# Kenbak-nanoduino_v2_001.net
KiCad netlist of a schematic drawn in EAGLE
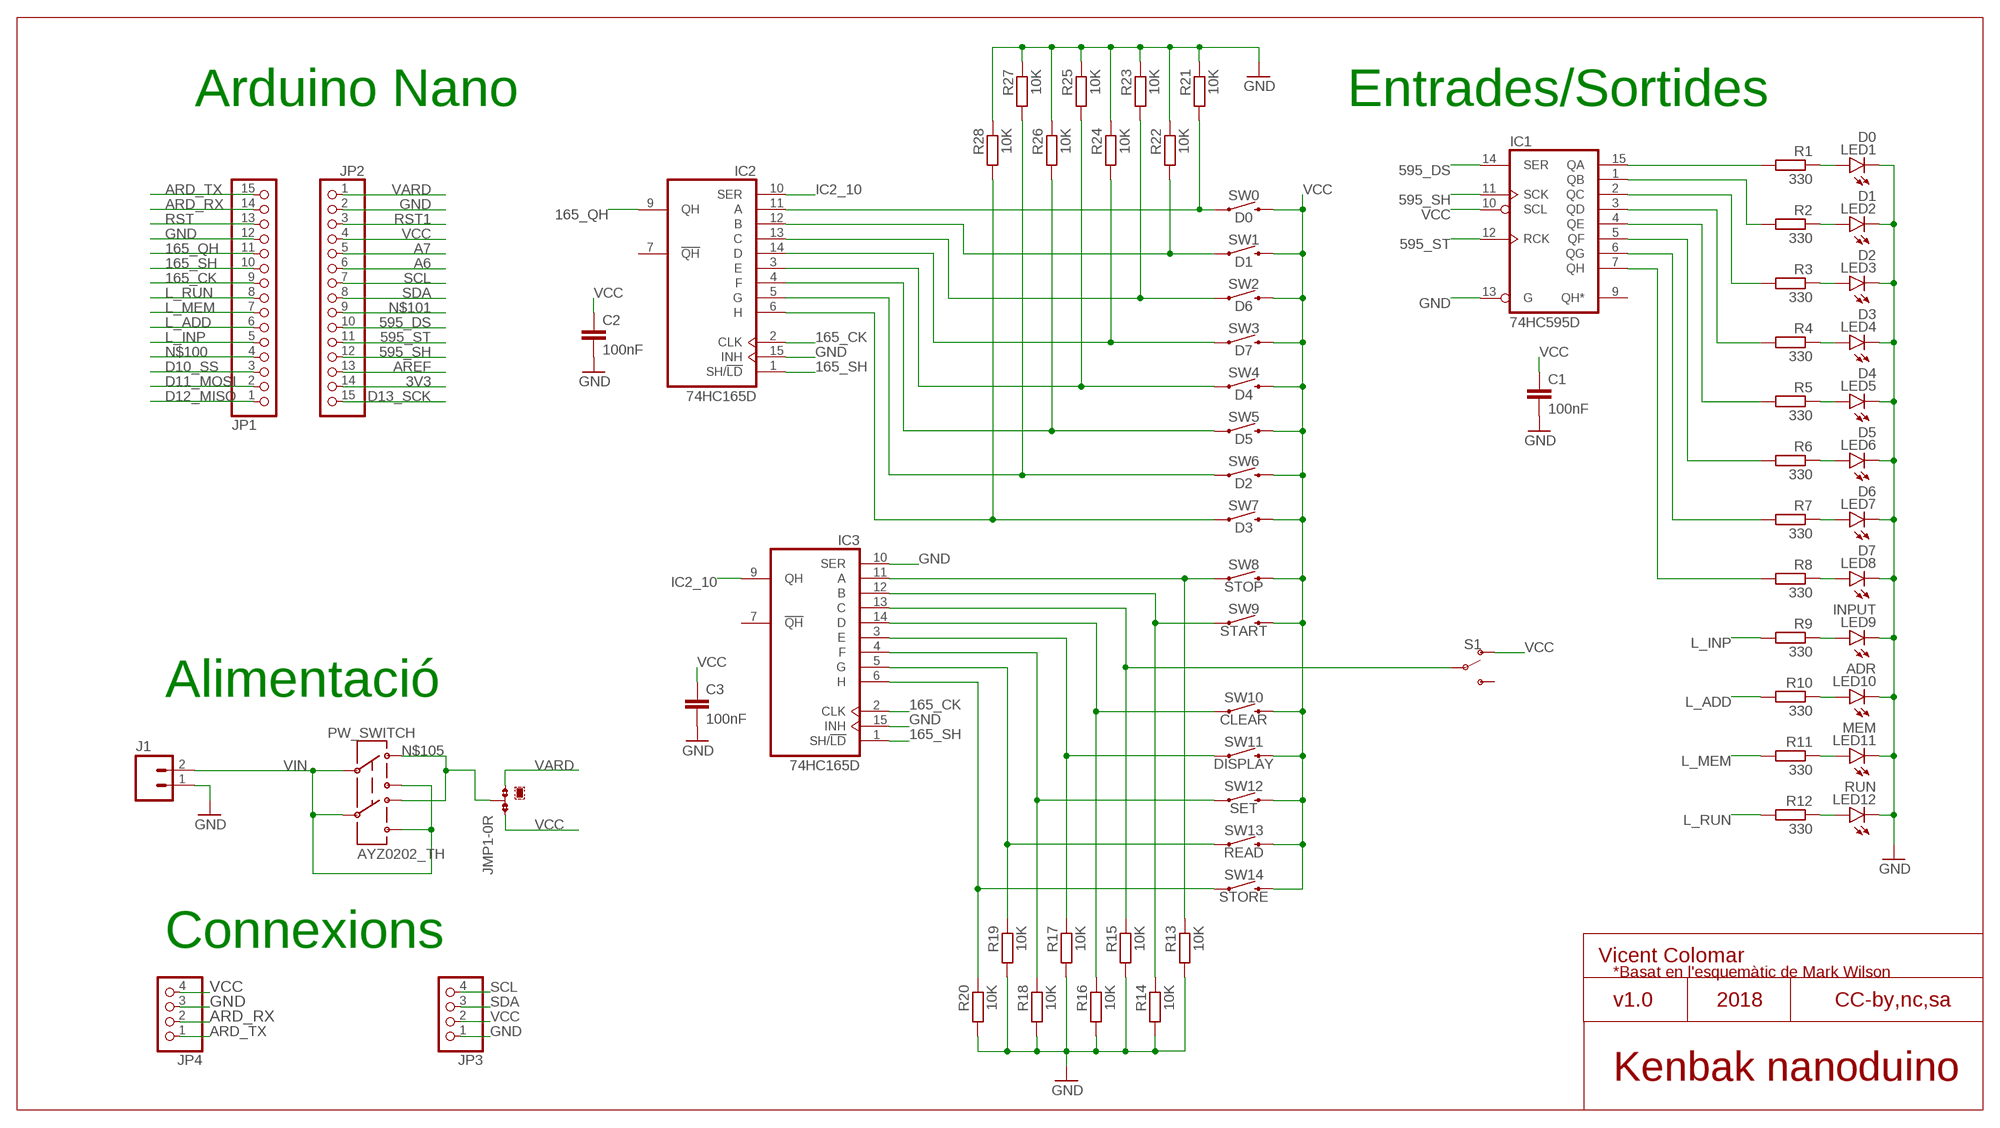
[diagram p0: schematic, sheet 1]

(export (version "E")
  (design (tool "Eeschema 10.0.6"))
  (components
    (comp (ref "C1")
      (value "100nF")
      (footprint "eagle-import:C1206")
      (libsource (lib "eagle-import") (part "C-EUC1206"))
    )
    (comp (ref "C2")
      (value "100nF")
      (footprint "eagle-import:C1206")
      (libsource (lib "eagle-import") (part "C-EUC1206"))
    )
    (comp (ref "C3")
      (value "100nF")
      (footprint "eagle-import:C1206")
      (libsource (lib "eagle-import") (part "C-EUC1206"))
    )
    (comp (ref "IC1")
      (value "74HC595D")
      (footprint "eagle-import:SO16")
      (libsource (lib "eagle-import") (part "74595DHC"))
    )
    (comp (ref "IC2")
      (value "74HC165D")
      (footprint "eagle-import:SO16")
      (libsource (lib "eagle-import") (part "74165DHC"))
    )
    (comp (ref "IC3")
      (value "74HC165D")
      (footprint "eagle-import:SO16")
      (libsource (lib "eagle-import") (part "74165DHC"))
    )
    (comp (ref "J1")
      (value "M02LOCK_LONGPADS")
      (footprint "eagle-import:1X02_LOCK_LONGPADS")
      (libsource (lib "eagle-import") (part "M02LOCK_LONGPADS"))
    )
    (comp (ref "JMP1")
      (value "0R-JUMPA")
      (footprint "eagle-import:A0R-JMP")
      (libsource (lib "eagle-import") (part "0R-JUMPA"))
    )
    (comp (ref "JP1")
      (value "PINHD-1X15_2.54-SMD")
      (footprint "eagle-import:1X15SMD")
      (libsource (lib "eagle-import") (part "PINHD-1X15_2.54-SMD"))
    )
    (comp (ref "JP2")
      (value "PINHD-1X15_2.54-SMD")
      (footprint "eagle-import:1X15SMD")
      (libsource (lib "eagle-import") (part "PINHD-1X15_2.54-SMD"))
    )
    (comp (ref "JP3")
      (value "PINHD-1X04_2.54-SMD")
      (footprint "eagle-import:1X04SMD")
      (libsource (lib "eagle-import") (part "PINHD-1X04_2.54-SMD"))
    )
    (comp (ref "JP4")
      (value "PINHD-1X04_2.54-SMD")
      (footprint "eagle-import:1X04SMD")
      (libsource (lib "eagle-import") (part "PINHD-1X04_2.54-SMD"))
    )
    (comp (ref "LED1")
      (value "D0")
      (footprint "eagle-import:LED3MM")
      (libsource (lib "eagle-import") (part "LED3MM"))
    )
    (comp (ref "LED2")
      (value "D1")
      (footprint "eagle-import:LED3MM")
      (libsource (lib "eagle-import") (part "LED3MM"))
    )
    (comp (ref "LED3")
      (value "D2")
      (footprint "eagle-import:LED3MM")
      (libsource (lib "eagle-import") (part "LED3MM"))
    )
    (comp (ref "LED4")
      (value "D3")
      (footprint "eagle-import:LED3MM")
      (libsource (lib "eagle-import") (part "LED3MM"))
    )
    (comp (ref "LED5")
      (value "D4")
      (footprint "eagle-import:LED3MM")
      (libsource (lib "eagle-import") (part "LED3MM"))
    )
    (comp (ref "LED6")
      (value "D5")
      (footprint "eagle-import:LED3MM")
      (libsource (lib "eagle-import") (part "LED3MM"))
    )
    (comp (ref "LED7")
      (value "D6")
      (footprint "eagle-import:LED3MM")
      (libsource (lib "eagle-import") (part "LED3MM"))
    )
    (comp (ref "LED8")
      (value "D7")
      (footprint "eagle-import:LED3MM")
      (libsource (lib "eagle-import") (part "LED3MM"))
    )
    (comp (ref "LED9")
      (value "INPUT")
      (footprint "eagle-import:LED3MM")
      (libsource (lib "eagle-import") (part "LED3MM"))
    )
    (comp (ref "LED10")
      (value "ADR")
      (footprint "eagle-import:LED3MM")
      (libsource (lib "eagle-import") (part "LED3MM"))
    )
    (comp (ref "LED11")
      (value "MEM")
      (footprint "eagle-import:LED3MM")
      (libsource (lib "eagle-import") (part "LED3MM"))
    )
    (comp (ref "LED12")
      (value "RUN")
      (footprint "eagle-import:LED3MM")
      (libsource (lib "eagle-import") (part "LED3MM"))
    )
    (comp (ref "PW_SWITCH")
      (value "AYZ0202_TH")
      (footprint "eagle-import:AYZ0202_TH")
      (libsource (lib "eagle-import") (part "AYZ0202_TH"))
    )
    (comp (ref "R1")
      (value "330")
      (footprint "eagle-import:R1206")
      (libsource (lib "eagle-import") (part "R-EU_R1206"))
    )
    (comp (ref "R2")
      (value "330")
      (footprint "eagle-import:R1206")
      (libsource (lib "eagle-import") (part "R-EU_R1206"))
    )
    (comp (ref "R3")
      (value "330")
      (footprint "eagle-import:R1206")
      (libsource (lib "eagle-import") (part "R-EU_R1206"))
    )
    (comp (ref "R4")
      (value "330")
      (footprint "eagle-import:R1206")
      (libsource (lib "eagle-import") (part "R-EU_R1206"))
    )
    (comp (ref "R5")
      (value "330")
      (footprint "eagle-import:R1206")
      (libsource (lib "eagle-import") (part "R-EU_R1206"))
    )
    (comp (ref "R6")
      (value "330")
      (footprint "eagle-import:R1206")
      (libsource (lib "eagle-import") (part "R-EU_R1206"))
    )
    (comp (ref "R7")
      (value "330")
      (footprint "eagle-import:R1206")
      (libsource (lib "eagle-import") (part "R-EU_R1206"))
    )
    (comp (ref "R8")
      (value "330")
      (footprint "eagle-import:R1206")
      (libsource (lib "eagle-import") (part "R-EU_R1206"))
    )
    (comp (ref "R9")
      (value "330")
      (footprint "eagle-import:R1206")
      (libsource (lib "eagle-import") (part "R-EU_R1206"))
    )
    (comp (ref "R10")
      (value "330")
      (footprint "eagle-import:R1206")
      (libsource (lib "eagle-import") (part "R-EU_R1206"))
    )
    (comp (ref "R11")
      (value "330")
      (footprint "eagle-import:R1206")
      (libsource (lib "eagle-import") (part "R-EU_R1206"))
    )
    (comp (ref "R12")
      (value "330")
      (footprint "eagle-import:R1206")
      (libsource (lib "eagle-import") (part "R-EU_R1206"))
    )
    (comp (ref "R13")
      (value "10K")
      (footprint "eagle-import:R1206")
      (libsource (lib "eagle-import") (part "R-EU_R1206"))
    )
    (comp (ref "R14")
      (value "10K")
      (footprint "eagle-import:R1206")
      (libsource (lib "eagle-import") (part "R-EU_R1206"))
    )
    (comp (ref "R15")
      (value "10K")
      (footprint "eagle-import:R1206")
      (libsource (lib "eagle-import") (part "R-EU_R1206"))
    )
    (comp (ref "R16")
      (value "10K")
      (footprint "eagle-import:R1206")
      (libsource (lib "eagle-import") (part "R-EU_R1206"))
    )
    (comp (ref "R17")
      (value "10K")
      (footprint "eagle-import:R1206")
      (libsource (lib "eagle-import") (part "R-EU_R1206"))
    )
    (comp (ref "R18")
      (value "10K")
      (footprint "eagle-import:R1206")
      (libsource (lib "eagle-import") (part "R-EU_R1206"))
    )
    (comp (ref "R19")
      (value "10K")
      (footprint "eagle-import:R1206")
      (libsource (lib "eagle-import") (part "R-EU_R1206"))
    )
    (comp (ref "R20")
      (value "10K")
      (footprint "eagle-import:R1206")
      (libsource (lib "eagle-import") (part "R-EU_R1206"))
    )
    (comp (ref "R21")
      (value "10K")
      (footprint "eagle-import:R1206")
      (libsource (lib "eagle-import") (part "R-EU_R1206"))
    )
    (comp (ref "R22")
      (value "10K")
      (footprint "eagle-import:R1206")
      (libsource (lib "eagle-import") (part "R-EU_R1206"))
    )
    (comp (ref "R23")
      (value "10K")
      (footprint "eagle-import:R1206")
      (libsource (lib "eagle-import") (part "R-EU_R1206"))
    )
    (comp (ref "R24")
      (value "10K")
      (footprint "eagle-import:R1206")
      (libsource (lib "eagle-import") (part "R-EU_R1206"))
    )
    (comp (ref "R25")
      (value "10K")
      (footprint "eagle-import:R1206")
      (libsource (lib "eagle-import") (part "R-EU_R1206"))
    )
    (comp (ref "R26")
      (value "10K")
      (footprint "eagle-import:R1206")
      (libsource (lib "eagle-import") (part "R-EU_R1206"))
    )
    (comp (ref "R27")
      (value "10K")
      (footprint "eagle-import:R1206")
      (libsource (lib "eagle-import") (part "R-EU_R1206"))
    )
    (comp (ref "R28")
      (value "10K")
      (footprint "eagle-import:R1206")
      (libsource (lib "eagle-import") (part "R-EU_R1206"))
    )
    (comp (ref "S1")
      (value "SWITCH-SPDT-PTH-11.6X4.0MM")
      (footprint "eagle-import:SWITCH_SPDT_PTH_11.6X4.0MM")
      (libsource (lib "eagle-import") (part "SWITCH-SPDT-PTH-11.6X4.0MM"))
    )
    (comp (ref "SW0")
      (value "D0")
      (footprint "eagle-import:TACTILE_SWITCH_SMD_6.0X3.5MM")
      (libsource (lib "eagle-import") (part "BOTOSMD"))
    )
    (comp (ref "SW1")
      (value "D1")
      (footprint "eagle-import:TACTILE_SWITCH_SMD_6.0X3.5MM")
      (libsource (lib "eagle-import") (part "BOTOSMD"))
    )
    (comp (ref "SW2")
      (value "D6")
      (footprint "eagle-import:TACTILE_SWITCH_SMD_6.0X3.5MM")
      (libsource (lib "eagle-import") (part "BOTOSMD"))
    )
    (comp (ref "SW3")
      (value "D7")
      (footprint "eagle-import:TACTILE_SWITCH_SMD_6.0X3.5MM")
      (libsource (lib "eagle-import") (part "BOTOSMD"))
    )
    (comp (ref "SW4")
      (value "D4")
      (footprint "eagle-import:TACTILE_SWITCH_SMD_6.0X3.5MM")
      (libsource (lib "eagle-import") (part "BOTOSMD"))
    )
    (comp (ref "SW5")
      (value "D5")
      (footprint "eagle-import:TACTILE_SWITCH_SMD_6.0X3.5MM")
      (libsource (lib "eagle-import") (part "BOTOSMD"))
    )
    (comp (ref "SW6")
      (value "D2")
      (footprint "eagle-import:TACTILE_SWITCH_SMD_6.0X3.5MM")
      (libsource (lib "eagle-import") (part "BOTOSMD"))
    )
    (comp (ref "SW7")
      (value "D3")
      (footprint "eagle-import:TACTILE_SWITCH_SMD_6.0X3.5MM")
      (libsource (lib "eagle-import") (part "BOTOSMD"))
    )
    (comp (ref "SW8")
      (value "STOP")
      (footprint "eagle-import:TACTILE_SWITCH_SMD_6.0X3.5MM")
      (libsource (lib "eagle-import") (part "BOTOSMD"))
    )
    (comp (ref "SW9")
      (value "START")
      (footprint "eagle-import:TACTILE_SWITCH_SMD_6.0X3.5MM")
      (libsource (lib "eagle-import") (part "BOTOSMD"))
    )
    (comp (ref "SW10")
      (value "CLEAR")
      (footprint "eagle-import:TACTILE_SWITCH_SMD_6.0X3.5MM")
      (libsource (lib "eagle-import") (part "BOTOSMD"))
    )
    (comp (ref "SW11")
      (value "DISPLAY")
      (footprint "eagle-import:TACTILE_SWITCH_SMD_6.0X3.5MM")
      (libsource (lib "eagle-import") (part "BOTOSMD"))
    )
    (comp (ref "SW12")
      (value "SET")
      (footprint "eagle-import:TACTILE_SWITCH_SMD_6.0X3.5MM")
      (libsource (lib "eagle-import") (part "BOTOSMD"))
    )
    (comp (ref "SW13")
      (value "READ")
      (footprint "eagle-import:TACTILE_SWITCH_SMD_6.0X3.5MM")
      (libsource (lib "eagle-import") (part "BOTOSMD"))
    )
    (comp (ref "SW14")
      (value "STORE")
      (footprint "eagle-import:TACTILE_SWITCH_SMD_6.0X3.5MM")
      (libsource (lib "eagle-import") (part "BOTOSMD"))
    )
  )
  (nets
    (net (code "1") (name "/3V3") (class "Default")
      (node (ref "JP2") (pin "14") (pinfunction "14_14") (pintype "passive"))
    )
    (net (code "2") (name "/165_CK") (class "Default")
      (node (ref "IC2") (pin "2") (pinfunction "CLK_2") (pintype "input"))
      (node (ref "IC3") (pin "2") (pinfunction "CLK_2") (pintype "input"))
      (node (ref "JP1") (pin "9") (pinfunction "9_9") (pintype "passive"))
    )
    (net (code "3") (name "/165_QH") (class "Default")
      (node (ref "IC2") (pin "9") (pinfunction "QH_9") (pintype "output"))
      (node (ref "JP1") (pin "11") (pinfunction "11_11") (pintype "passive"))
    )
    (net (code "4") (name "/165_SH") (class "Default")
      (node (ref "IC2") (pin "1") (pinfunction "SH/~{LD}_1") (pintype "input"))
      (node (ref "IC3") (pin "1") (pinfunction "SH/~{LD}_1") (pintype "input"))
      (node (ref "JP1") (pin "10") (pinfunction "10_10") (pintype "passive"))
    )
    (net (code "5") (name "/595_DS") (class "Default")
      (node (ref "IC1") (pin "14") (pinfunction "SER_14") (pintype "input"))
      (node (ref "JP2") (pin "10") (pinfunction "10_10") (pintype "passive"))
    )
    (net (code "6") (name "/595_SH") (class "Default")
      (node (ref "IC1") (pin "11") (pinfunction "SCK_11") (pintype "input"))
      (node (ref "JP2") (pin "12") (pinfunction "12_12") (pintype "passive"))
    )
    (net (code "7") (name "/595_ST") (class "Default")
      (node (ref "IC1") (pin "12") (pinfunction "RCK_12") (pintype "input"))
      (node (ref "JP2") (pin "11") (pinfunction "11_11") (pintype "passive"))
    )
    (net (code "8") (name "/A6") (class "Default")
      (node (ref "JP2") (pin "6") (pinfunction "6_6") (pintype "passive"))
    )
    (net (code "9") (name "/A7") (class "Default")
      (node (ref "JP2") (pin "5") (pinfunction "5_5") (pintype "passive"))
    )
    (net (code "10") (name "/ARD_RX") (class "Default")
      (node (ref "JP1") (pin "14") (pinfunction "14_14") (pintype "passive"))
      (node (ref "JP4") (pin "2") (pinfunction "2_2") (pintype "passive"))
    )
    (net (code "11") (name "/ARD_TX") (class "Default")
      (node (ref "JP1") (pin "15") (pinfunction "15_15") (pintype "passive"))
      (node (ref "JP4") (pin "1") (pinfunction "1_1") (pintype "passive"))
    )
    (net (code "12") (name "/AREF") (class "Default")
      (node (ref "JP2") (pin "13") (pinfunction "13_13") (pintype "passive"))
    )
    (net (code "13") (name "/D10_SS") (class "Default")
      (node (ref "JP1") (pin "3") (pinfunction "3_3") (pintype "passive"))
    )
    (net (code "14") (name "/D11_MOSI") (class "Default")
      (node (ref "JP1") (pin "2") (pinfunction "2_2") (pintype "passive"))
    )
    (net (code "15") (name "/D12_MISO") (class "Default")
      (node (ref "JP1") (pin "1") (pinfunction "1_1") (pintype "passive"))
    )
    (net (code "16") (name "/D13_SCK") (class "Default")
      (node (ref "JP2") (pin "15") (pinfunction "15_15") (pintype "passive"))
    )
    (net (code "17") (name "/IC2_10") (class "Default")
      (node (ref "IC2") (pin "10") (pinfunction "SER_10") (pintype "input"))
      (node (ref "IC3") (pin "9") (pinfunction "QH_9") (pintype "output"))
    )
    (net (code "18") (name "/L_ADD") (class "Default")
      (node (ref "JP1") (pin "6") (pinfunction "6_6") (pintype "passive"))
      (node (ref "R10") (pin "2") (pinfunction "2_2") (pintype "passive"))
    )
    (net (code "19") (name "/L_INP") (class "Default")
      (node (ref "JP1") (pin "5") (pinfunction "5_5") (pintype "passive"))
      (node (ref "R9") (pin "2") (pinfunction "2_2") (pintype "passive"))
    )
    (net (code "20") (name "/L_MEM") (class "Default")
      (node (ref "JP1") (pin "7") (pinfunction "7_7") (pintype "passive"))
      (node (ref "R11") (pin "2") (pinfunction "2_2") (pintype "passive"))
    )
    (net (code "21") (name "/L_RUN") (class "Default")
      (node (ref "JP1") (pin "8") (pinfunction "8_8") (pintype "passive"))
      (node (ref "R12") (pin "2") (pinfunction "2_2") (pintype "passive"))
    )
    (net (code "22") (name "/N$100") (class "Default")
      (node (ref "JP1") (pin "4") (pinfunction "4_4") (pintype "passive"))
    )
    (net (code "23") (name "/N$101") (class "Default")
      (node (ref "JP2") (pin "9") (pinfunction "9_9") (pintype "passive"))
    )
    (net (code "24") (name "/N$105") (class "Default")
      (node (ref "JMP1") (pin "2") (pinfunction "2_2") (pintype "passive"))
      (node (ref "PW_SWITCH") (pin "D1") (pinfunction "D1_D1") (pintype "bidirectional"))
      (node (ref "PW_SWITCH") (pin "D2") (pinfunction "D2_D2") (pintype "bidirectional"))
    )
    (net (code "25") (name "/RST") (class "Default")
      (node (ref "JP1") (pin "13") (pinfunction "13_13") (pintype "passive"))
    )
    (net (code "26") (name "/RST1") (class "Default")
      (node (ref "JP2") (pin "3") (pinfunction "3_3") (pintype "passive"))
    )
    (net (code "27") (name "/SCL") (class "Default")
      (node (ref "JP2") (pin "7") (pinfunction "7_7") (pintype "passive"))
      (node (ref "JP3") (pin "4") (pinfunction "4_4") (pintype "passive"))
    )
    (net (code "28") (name "/SDA") (class "Default")
      (node (ref "JP2") (pin "8") (pinfunction "8_8") (pintype "passive"))
      (node (ref "JP3") (pin "3") (pinfunction "3_3") (pintype "passive"))
    )
    (net (code "29") (name "/VARD") (class "Default")
      (node (ref "JMP1") (pin "3") (pinfunction "3_3") (pintype "passive"))
      (node (ref "JP2") (pin "1") (pinfunction "1_1") (pintype "passive"))
    )
    (net (code "30") (name "/VCC") (class "Default")
      (node (ref "C1") (pin "1") (pinfunction "1_1") (pintype "passive"))
      (node (ref "C2") (pin "1") (pinfunction "1_1") (pintype "passive"))
      (node (ref "C3") (pin "1") (pinfunction "1_1") (pintype "passive"))
      (node (ref "IC1") (pin "10") (pinfunction "SCL_10") (pintype "input"))
      (node (ref "JMP1") (pin "1") (pinfunction "1_1") (pintype "passive"))
      (node (ref "JP2") (pin "4") (pinfunction "4_4") (pintype "passive"))
      (node (ref "JP3") (pin "2") (pinfunction "2_2") (pintype "passive"))
      (node (ref "JP4") (pin "4") (pinfunction "4_4") (pintype "passive"))
      (node (ref "S1") (pin "1") (pinfunction "O_1") (pintype "passive"))
      (node (ref "SW0") (pin "2") (pinfunction "2_2") (pintype "passive"))
      (node (ref "SW1") (pin "2") (pinfunction "2_2") (pintype "passive"))
      (node (ref "SW10") (pin "2") (pinfunction "2_2") (pintype "passive"))
      (node (ref "SW11") (pin "2") (pinfunction "2_2") (pintype "passive"))
      (node (ref "SW12") (pin "2") (pinfunction "2_2") (pintype "passive"))
      (node (ref "SW13") (pin "2") (pinfunction "2_2") (pintype "passive"))
      (node (ref "SW14") (pin "2") (pinfunction "2_2") (pintype "passive"))
      (node (ref "SW2") (pin "2") (pinfunction "2_2") (pintype "passive"))
      (node (ref "SW3") (pin "2") (pinfunction "2_2") (pintype "passive"))
      (node (ref "SW4") (pin "2") (pinfunction "2_2") (pintype "passive"))
      (node (ref "SW5") (pin "2") (pinfunction "2_2") (pintype "passive"))
      (node (ref "SW6") (pin "2") (pinfunction "2_2") (pintype "passive"))
      (node (ref "SW7") (pin "2") (pinfunction "2_2") (pintype "passive"))
      (node (ref "SW8") (pin "2") (pinfunction "2_2") (pintype "passive"))
      (node (ref "SW9") (pin "2") (pinfunction "2_2") (pintype "passive"))
    )
    (net (code "31") (name "/VIN") (class "Default")
      (node (ref "J1") (pin "2") (pinfunction "2_2") (pintype "passive"))
      (node (ref "PW_SWITCH") (pin "B1") (pinfunction "B1_B1") (pintype "bidirectional"))
      (node (ref "PW_SWITCH") (pin "B2") (pinfunction "B2_B2") (pintype "bidirectional"))
      (node (ref "PW_SWITCH") (pin "C1") (pinfunction "C1_C1") (pintype "bidirectional"))
      (node (ref "PW_SWITCH") (pin "C2") (pinfunction "C2_C2") (pintype "bidirectional"))
    )
    (net (code "32") (name "GND") (class "Default")
      (node (ref "C1") (pin "2") (pinfunction "2_2") (pintype "passive"))
      (node (ref "C2") (pin "2") (pinfunction "2_2") (pintype "passive"))
      (node (ref "C3") (pin "2") (pinfunction "2_2") (pintype "passive"))
      (node (ref "IC1") (pin "13") (pinfunction "G_13") (pintype "input"))
      (node (ref "IC2") (pin "15") (pinfunction "INH_15") (pintype "input"))
      (node (ref "IC3") (pin "10") (pinfunction "SER_10") (pintype "input"))
      (node (ref "IC3") (pin "15") (pinfunction "INH_15") (pintype "input"))
      (node (ref "J1") (pin "1") (pinfunction "1_1") (pintype "passive"))
      (node (ref "JP1") (pin "12") (pinfunction "12_12") (pintype "passive"))
      (node (ref "JP2") (pin "2") (pinfunction "2_2") (pintype "passive"))
      (node (ref "JP3") (pin "1") (pinfunction "1_1") (pintype "passive"))
      (node (ref "JP4") (pin "3") (pinfunction "3_3") (pintype "passive"))
      (node (ref "LED1") (pin "K") (pinfunction "C_K") (pintype "passive"))
      (node (ref "LED10") (pin "K") (pinfunction "C_K") (pintype "passive"))
      (node (ref "LED11") (pin "K") (pinfunction "C_K") (pintype "passive"))
      (node (ref "LED12") (pin "K") (pinfunction "C_K") (pintype "passive"))
      (node (ref "LED2") (pin "K") (pinfunction "C_K") (pintype "passive"))
      (node (ref "LED3") (pin "K") (pinfunction "C_K") (pintype "passive"))
      (node (ref "LED4") (pin "K") (pinfunction "C_K") (pintype "passive"))
      (node (ref "LED5") (pin "K") (pinfunction "C_K") (pintype "passive"))
      (node (ref "LED6") (pin "K") (pinfunction "C_K") (pintype "passive"))
      (node (ref "LED7") (pin "K") (pinfunction "C_K") (pintype "passive"))
      (node (ref "LED8") (pin "K") (pinfunction "C_K") (pintype "passive"))
      (node (ref "LED9") (pin "K") (pinfunction "C_K") (pintype "passive"))
      (node (ref "R13") (pin "2") (pinfunction "2_2") (pintype "passive"))
      (node (ref "R14") (pin "2") (pinfunction "2_2") (pintype "passive"))
      (node (ref "R15") (pin "2") (pinfunction "2_2") (pintype "passive"))
      (node (ref "R16") (pin "2") (pinfunction "2_2") (pintype "passive"))
      (node (ref "R17") (pin "2") (pinfunction "2_2") (pintype "passive"))
      (node (ref "R18") (pin "2") (pinfunction "2_2") (pintype "passive"))
      (node (ref "R19") (pin "2") (pinfunction "2_2") (pintype "passive"))
      (node (ref "R20") (pin "2") (pinfunction "2_2") (pintype "passive"))
      (node (ref "R21") (pin "1") (pinfunction "1_1") (pintype "passive"))
      (node (ref "R22") (pin "1") (pinfunction "1_1") (pintype "passive"))
      (node (ref "R23") (pin "1") (pinfunction "1_1") (pintype "passive"))
      (node (ref "R24") (pin "1") (pinfunction "1_1") (pintype "passive"))
      (node (ref "R25") (pin "1") (pinfunction "1_1") (pintype "passive"))
      (node (ref "R26") (pin "1") (pinfunction "1_1") (pintype "passive"))
      (node (ref "R27") (pin "1") (pinfunction "1_1") (pintype "passive"))
      (node (ref "R28") (pin "1") (pinfunction "1_1") (pintype "passive"))
    )
    (net (code "33") (name "Net-(IC1A-QA)") (class "Default")
      (node (ref "IC1") (pin "15") (pinfunction "QA_15") (pintype "tri_state"))
      (node (ref "R1") (pin "2") (pinfunction "2_2") (pintype "passive"))
    )
    (net (code "34") (name "Net-(IC1A-QB)") (class "Default")
      (node (ref "IC1") (pin "1") (pinfunction "QB_1") (pintype "tri_state"))
      (node (ref "R2") (pin "2") (pinfunction "2_2") (pintype "passive"))
    )
    (net (code "35") (name "Net-(IC1A-QC)") (class "Default")
      (node (ref "IC1") (pin "2") (pinfunction "QC_2") (pintype "tri_state"))
      (node (ref "R3") (pin "2") (pinfunction "2_2") (pintype "passive"))
    )
    (net (code "36") (name "Net-(IC1A-QD)") (class "Default")
      (node (ref "IC1") (pin "3") (pinfunction "QD_3") (pintype "tri_state"))
      (node (ref "R4") (pin "2") (pinfunction "2_2") (pintype "passive"))
    )
    (net (code "37") (name "Net-(IC1A-QE)") (class "Default")
      (node (ref "IC1") (pin "4") (pinfunction "QE_4") (pintype "tri_state"))
      (node (ref "R5") (pin "2") (pinfunction "2_2") (pintype "passive"))
    )
    (net (code "38") (name "Net-(IC1A-QF)") (class "Default")
      (node (ref "IC1") (pin "5") (pinfunction "QF_5") (pintype "tri_state"))
      (node (ref "R6") (pin "2") (pinfunction "2_2") (pintype "passive"))
    )
    (net (code "39") (name "Net-(IC1A-QG)") (class "Default")
      (node (ref "IC1") (pin "6") (pinfunction "QG_6") (pintype "tri_state"))
      (node (ref "R7") (pin "2") (pinfunction "2_2") (pintype "passive"))
    )
    (net (code "40") (name "Net-(IC1A-QH)") (class "Default")
      (node (ref "IC1") (pin "7") (pinfunction "QH_7") (pintype "tri_state"))
      (node (ref "R8") (pin "2") (pinfunction "2_2") (pintype "passive"))
    )
    (net (code "41") (name "Net-(IC2A-A)") (class "Default")
      (node (ref "IC2") (pin "11") (pinfunction "A_11") (pintype "input"))
      (node (ref "R21") (pin "2") (pinfunction "2_2") (pintype "passive"))
      (node (ref "SW0") (pin "1") (pinfunction "1_1") (pintype "passive"))
    )
    (net (code "42") (name "Net-(IC2A-B)") (class "Default")
      (node (ref "IC2") (pin "12") (pinfunction "B_12") (pintype "input"))
      (node (ref "R22") (pin "2") (pinfunction "2_2") (pintype "passive"))
      (node (ref "SW1") (pin "1") (pinfunction "1_1") (pintype "passive"))
    )
    (net (code "43") (name "Net-(IC2A-C)") (class "Default")
      (node (ref "IC2") (pin "13") (pinfunction "C_13") (pintype "input"))
      (node (ref "R23") (pin "2") (pinfunction "2_2") (pintype "passive"))
      (node (ref "SW2") (pin "1") (pinfunction "1_1") (pintype "passive"))
    )
    (net (code "44") (name "Net-(IC2A-D)") (class "Default")
      (node (ref "IC2") (pin "14") (pinfunction "D_14") (pintype "input"))
      (node (ref "R24") (pin "2") (pinfunction "2_2") (pintype "passive"))
      (node (ref "SW3") (pin "1") (pinfunction "1_1") (pintype "passive"))
    )
    (net (code "45") (name "Net-(IC2A-E)") (class "Default")
      (node (ref "IC2") (pin "3") (pinfunction "E_3") (pintype "input"))
      (node (ref "R25") (pin "2") (pinfunction "2_2") (pintype "passive"))
      (node (ref "SW4") (pin "1") (pinfunction "1_1") (pintype "passive"))
    )
    (net (code "46") (name "Net-(IC2A-F)") (class "Default")
      (node (ref "IC2") (pin "4") (pinfunction "F_4") (pintype "input"))
      (node (ref "R26") (pin "2") (pinfunction "2_2") (pintype "passive"))
      (node (ref "SW5") (pin "1") (pinfunction "1_1") (pintype "passive"))
    )
    (net (code "47") (name "Net-(IC2A-G)") (class "Default")
      (node (ref "IC2") (pin "5") (pinfunction "G_5") (pintype "input"))
      (node (ref "R27") (pin "2") (pinfunction "2_2") (pintype "passive"))
      (node (ref "SW6") (pin "1") (pinfunction "1_1") (pintype "passive"))
    )
    (net (code "48") (name "Net-(IC2A-H)") (class "Default")
      (node (ref "IC2") (pin "6") (pinfunction "H_6") (pintype "input"))
      (node (ref "R28") (pin "2") (pinfunction "2_2") (pintype "passive"))
      (node (ref "SW7") (pin "1") (pinfunction "1_1") (pintype "passive"))
    )
    (net (code "49") (name "Net-(IC3A-A)") (class "Default")
      (node (ref "IC3") (pin "11") (pinfunction "A_11") (pintype "input"))
      (node (ref "R13") (pin "1") (pinfunction "1_1") (pintype "passive"))
      (node (ref "SW8") (pin "1") (pinfunction "1_1") (pintype "passive"))
    )
    (net (code "50") (name "Net-(IC3A-B)") (class "Default")
      (node (ref "IC3") (pin "12") (pinfunction "B_12") (pintype "input"))
      (node (ref "R14") (pin "1") (pinfunction "1_1") (pintype "passive"))
      (node (ref "SW9") (pin "1") (pinfunction "1_1") (pintype "passive"))
    )
    (net (code "51") (name "Net-(IC3A-C)") (class "Default")
      (node (ref "IC3") (pin "13") (pinfunction "C_13") (pintype "input"))
      (node (ref "R15") (pin "1") (pinfunction "1_1") (pintype "passive"))
      (node (ref "S1") (pin "2") (pinfunction "P_2") (pintype "passive"))
    )
    (net (code "52") (name "Net-(IC3A-D)") (class "Default")
      (node (ref "IC3") (pin "14") (pinfunction "D_14") (pintype "input"))
      (node (ref "R16") (pin "1") (pinfunction "1_1") (pintype "passive"))
      (node (ref "SW10") (pin "1") (pinfunction "1_1") (pintype "passive"))
    )
    (net (code "53") (name "Net-(IC3A-E)") (class "Default")
      (node (ref "IC3") (pin "3") (pinfunction "E_3") (pintype "input"))
      (node (ref "R17") (pin "1") (pinfunction "1_1") (pintype "passive"))
      (node (ref "SW11") (pin "1") (pinfunction "1_1") (pintype "passive"))
    )
    (net (code "54") (name "Net-(IC3A-F)") (class "Default")
      (node (ref "IC3") (pin "4") (pinfunction "F_4") (pintype "input"))
      (node (ref "R18") (pin "1") (pinfunction "1_1") (pintype "passive"))
      (node (ref "SW12") (pin "1") (pinfunction "1_1") (pintype "passive"))
    )
    (net (code "55") (name "Net-(IC3A-G)") (class "Default")
      (node (ref "IC3") (pin "5") (pinfunction "G_5") (pintype "input"))
      (node (ref "R19") (pin "1") (pinfunction "1_1") (pintype "passive"))
      (node (ref "SW13") (pin "1") (pinfunction "1_1") (pintype "passive"))
    )
    (net (code "56") (name "Net-(IC3A-H)") (class "Default")
      (node (ref "IC3") (pin "6") (pinfunction "H_6") (pintype "input"))
      (node (ref "R20") (pin "1") (pinfunction "1_1") (pintype "passive"))
      (node (ref "SW14") (pin "1") (pinfunction "1_1") (pintype "passive"))
    )
    (net (code "57") (name "Net-(LED1-PadA)") (class "Default")
      (node (ref "LED1") (pin "A") (pinfunction "A_A") (pintype "passive"))
      (node (ref "R1") (pin "1") (pinfunction "1_1") (pintype "passive"))
    )
    (net (code "58") (name "Net-(LED2-PadA)") (class "Default")
      (node (ref "LED2") (pin "A") (pinfunction "A_A") (pintype "passive"))
      (node (ref "R2") (pin "1") (pinfunction "1_1") (pintype "passive"))
    )
    (net (code "59") (name "Net-(LED3-PadA)") (class "Default")
      (node (ref "LED3") (pin "A") (pinfunction "A_A") (pintype "passive"))
      (node (ref "R3") (pin "1") (pinfunction "1_1") (pintype "passive"))
    )
    (net (code "60") (name "Net-(LED4-PadA)") (class "Default")
      (node (ref "LED4") (pin "A") (pinfunction "A_A") (pintype "passive"))
      (node (ref "R4") (pin "1") (pinfunction "1_1") (pintype "passive"))
    )
    (net (code "61") (name "Net-(LED5-PadA)") (class "Default")
      (node (ref "LED5") (pin "A") (pinfunction "A_A") (pintype "passive"))
      (node (ref "R5") (pin "1") (pinfunction "1_1") (pintype "passive"))
    )
    (net (code "62") (name "Net-(LED6-PadA)") (class "Default")
      (node (ref "LED6") (pin "A") (pinfunction "A_A") (pintype "passive"))
      (node (ref "R6") (pin "1") (pinfunction "1_1") (pintype "passive"))
    )
    (net (code "63") (name "Net-(LED7-PadA)") (class "Default")
      (node (ref "LED7") (pin "A") (pinfunction "A_A") (pintype "passive"))
      (node (ref "R7") (pin "1") (pinfunction "1_1") (pintype "passive"))
    )
    (net (code "64") (name "Net-(LED8-PadA)") (class "Default")
      (node (ref "LED8") (pin "A") (pinfunction "A_A") (pintype "passive"))
      (node (ref "R8") (pin "1") (pinfunction "1_1") (pintype "passive"))
    )
    (net (code "65") (name "Net-(LED9-PadA)") (class "Default")
      (node (ref "LED9") (pin "A") (pinfunction "A_A") (pintype "passive"))
      (node (ref "R9") (pin "1") (pinfunction "1_1") (pintype "passive"))
    )
    (net (code "66") (name "Net-(LED10-PadA)") (class "Default")
      (node (ref "LED10") (pin "A") (pinfunction "A_A") (pintype "passive"))
      (node (ref "R10") (pin "1") (pinfunction "1_1") (pintype "passive"))
    )
    (net (code "67") (name "Net-(LED11-PadA)") (class "Default")
      (node (ref "LED11") (pin "A") (pinfunction "A_A") (pintype "passive"))
      (node (ref "R11") (pin "1") (pinfunction "1_1") (pintype "passive"))
    )
    (net (code "68") (name "Net-(LED12-PadA)") (class "Default")
      (node (ref "LED12") (pin "A") (pinfunction "A_A") (pintype "passive"))
      (node (ref "R12") (pin "1") (pinfunction "1_1") (pintype "passive"))
    )
    (net (code "69") (name "unconnected-(IC1A-QH*-Pad9)") (class "Default")
      (node (ref "IC1") (pin "9") (pinfunction "QH*_9") (pintype "tri_state"))
    )
    (net (code "70") (name "unconnected-(IC2A-~{QH}-Pad7)") (class "Default")
      (node (ref "IC2") (pin "7") (pinfunction "~{QH}_7") (pintype "output"))
    )
    (net (code "71") (name "unconnected-(IC3A-~{QH}-Pad7)") (class "Default")
      (node (ref "IC3") (pin "7") (pinfunction "~{QH}_7") (pintype "output"))
    )
    (net (code "72") (name "unconnected-(S1-S-Pad3)") (class "Default")
      (node (ref "S1") (pin "3") (pinfunction "S_3") (pintype "passive"))
    )
  )
)
